# eeZeeISP_Tiny_FT230X.net
KiCad netlist of a schematic drawn in EAGLE
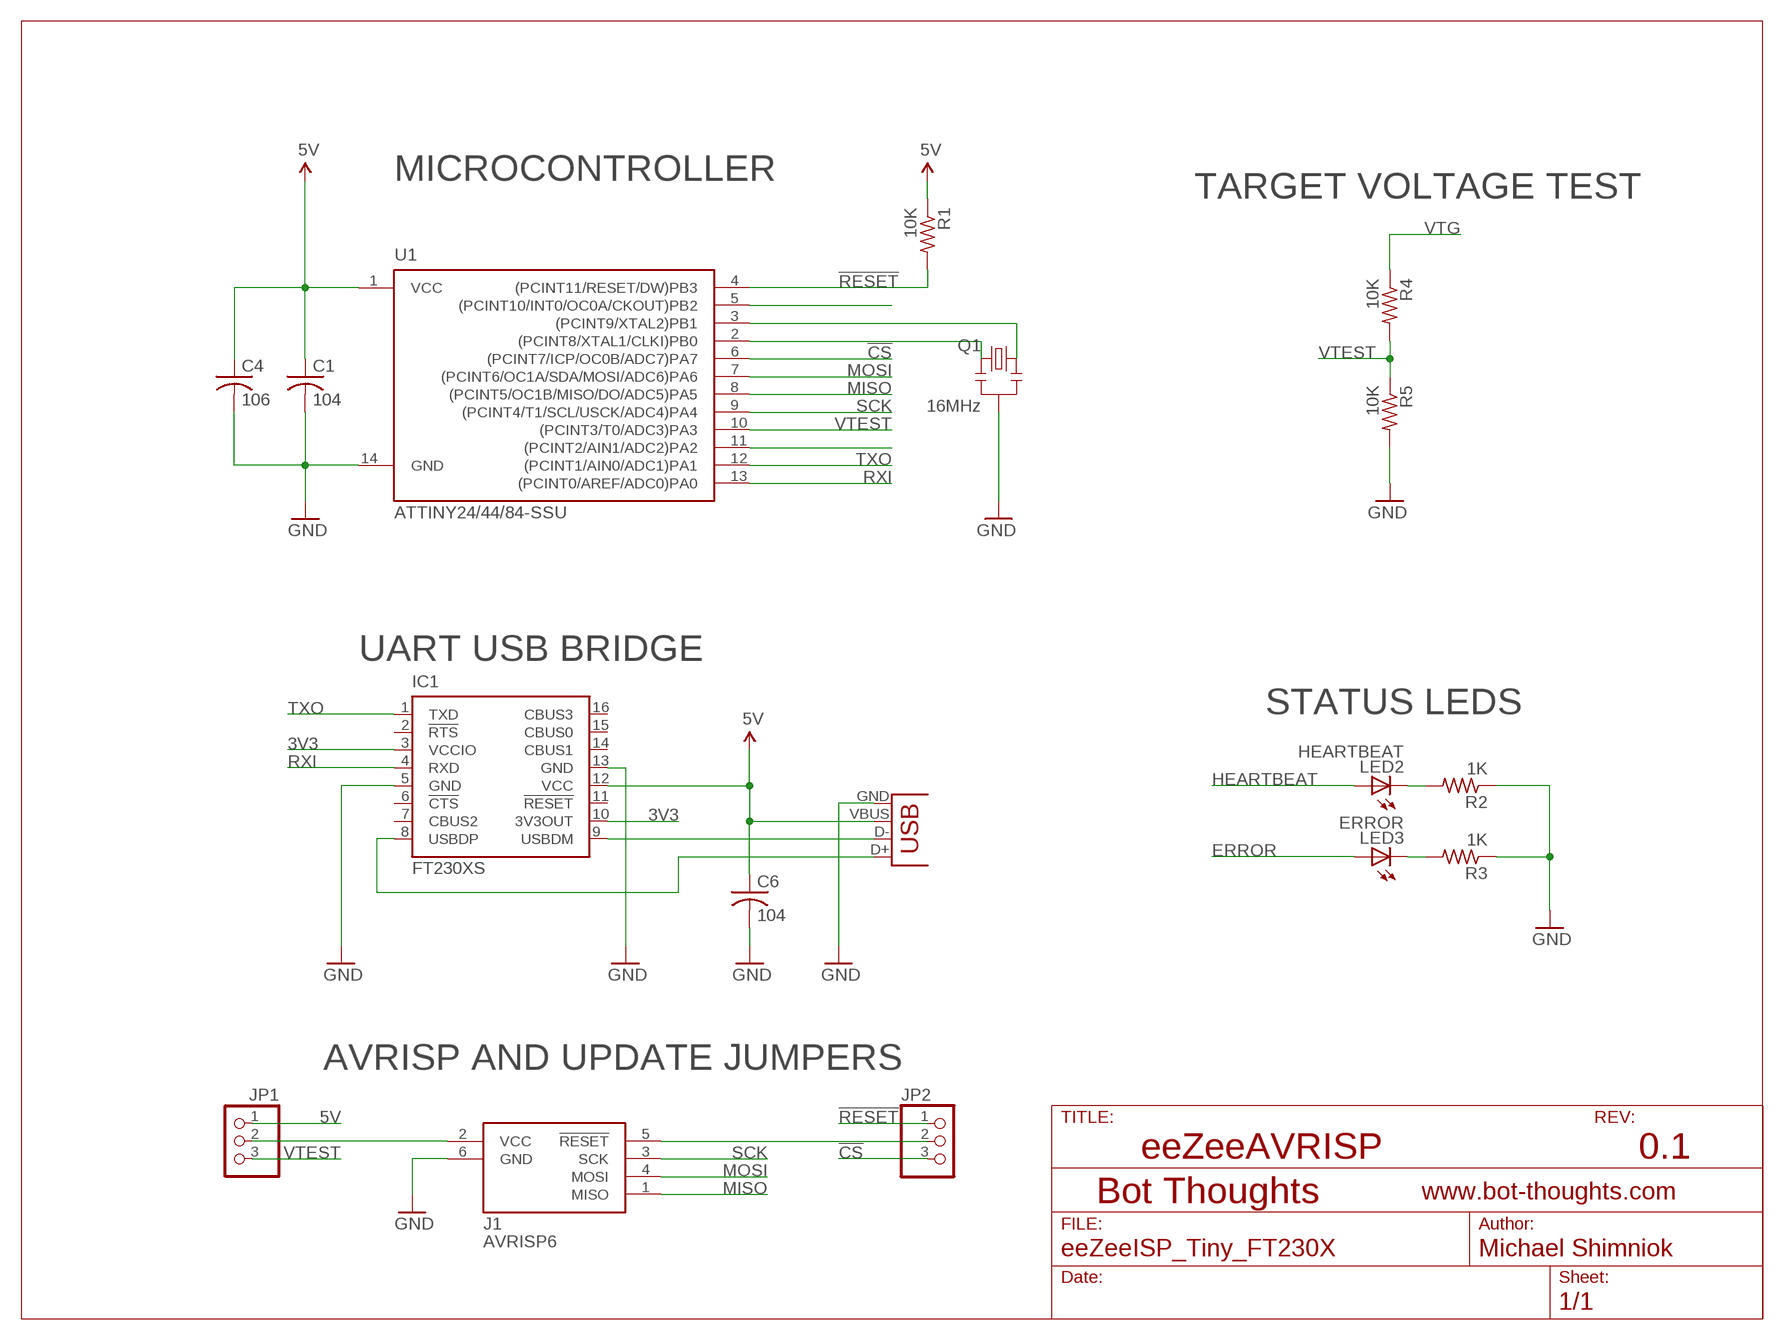
[diagram p0: schematic, sheet 1]

(export (version "E")
  (design (tool "Eeschema 10.0.6"))
  (components
    (comp (ref "C1")
      (value "104")
      (footprint "eagle-import:C0603")
      (libsource (lib "eagle-import") (part "C-USC0603"))
    )
    (comp (ref "C4")
      (value "106")
      (footprint "eagle-import:C0603")
      (libsource (lib "eagle-import") (part "C-USC0603"))
    )
    (comp (ref "C6")
      (value "104")
      (footprint "eagle-import:C0603")
      (libsource (lib "eagle-import") (part "C-USC0603"))
    )
    (comp (ref "IC1")
      (value "FT230XS")
      (footprint "eagle-import:SSOP16")
      (libsource (lib "eagle-import") (part "FT230XS"))
    )
    (comp (ref "J1")
      (value "AVRISP6")
      (footprint "eagle-import:CON6P2R")
      (libsource (lib "eagle-import") (part "AVRISP6"))
    )
    (comp (ref "JP1")
      (value "PINHD-1X03_2.00")
      (footprint "eagle-import:1X03M")
      (libsource (lib "eagle-import") (part "PINHD-1X03_2.00"))
    )
    (comp (ref "JP2")
      (value "PINHD-1X03_2.00")
      (footprint "eagle-import:1X03M")
      (libsource (lib "eagle-import") (part "PINHD-1X03_2.00"))
    )
    (comp (ref "LED2")
      (value "HEARTBEAT")
      (footprint "eagle-import:CHIPLED_1206")
      (libsource (lib "eagle-import") (part "LEDCHIPLED_1206"))
    )
    (comp (ref "LED3")
      (value "ERROR")
      (footprint "eagle-import:CHIPLED_1206")
      (libsource (lib "eagle-import") (part "LEDCHIPLED_1206"))
    )
    (comp (ref "Q1")
      (value "16MHz")
      (footprint "eagle-import:CSTCE_V_C")
      (libsource (lib "eagle-import") (part "RESONATOR_CSTCE_V_C"))
    )
    (comp (ref "R1")
      (value "10K")
      (footprint "eagle-import:R0603")
      (libsource (lib "eagle-import") (part "R-US_R0603"))
    )
    (comp (ref "R2")
      (value "1K")
      (footprint "eagle-import:R0603")
      (libsource (lib "eagle-import") (part "R-US_R0603"))
    )
    (comp (ref "R3")
      (value "1K")
      (footprint "eagle-import:R0603")
      (libsource (lib "eagle-import") (part "R-US_R0603"))
    )
    (comp (ref "R4")
      (value "10K")
      (footprint "eagle-import:R0603")
      (libsource (lib "eagle-import") (part "R-US_R0603"))
    )
    (comp (ref "R5")
      (value "10K")
      (footprint "eagle-import:R0603")
      (libsource (lib "eagle-import") (part "R-US_R0603"))
    )
    (comp (ref "U1")
      (value "ATTINY24/44/84-SSU")
      (footprint "eagle-import:SOIC14")
      (libsource (lib "eagle-import") (part "ATTINY24/44/84-SSU"))
    )
    (comp (ref "X2")
      (value "USB-SMD-NS")
      (footprint "eagle-import:USB-MINIB-NOSTOP")
      (libsource (lib "eagle-import") (part "USB-SMD-NS"))
    )
  )
  (nets
    (net (code "1") (name "/3V3") (class "Default")
      (node (ref "IC1") (pin "10") (pinfunction "3V3OUT_10") (pintype "output"))
      (node (ref "IC1") (pin "3") (pinfunction "VCCIO_3") (pintype "power_in"))
    )
    (net (code "2") (name "/ERROR") (class "Default")
      (node (ref "LED3") (pin "A") (pinfunction "A_A") (pintype "passive"))
      (node (ref "U1") (pin "11") (pinfunction "(PCINT2/AIN1/ADC2)PA2_11") (pintype "bidirectional"))
    )
    (net (code "3") (name "/HEARTBEAT") (class "Default")
      (node (ref "LED2") (pin "A") (pinfunction "A_A") (pintype "passive"))
      (node (ref "U1") (pin "5") (pinfunction "(PCINT10/INT0/OC0A/CKOUT)PB2_5") (pintype "bidirectional"))
    )
    (net (code "4") (name "/MISO") (class "Default")
      (node (ref "J1") (pin "1") (pinfunction "MISO_1") (pintype "input"))
      (node (ref "U1") (pin "8") (pinfunction "(PCINT5/OC1B/MISO/DO/ADC5)PA5_8") (pintype "bidirectional"))
    )
    (net (code "5") (name "/MOSI") (class "Default")
      (node (ref "J1") (pin "4") (pinfunction "MOSI_4") (pintype "output"))
      (node (ref "U1") (pin "7") (pinfunction "(PCINT6/OC1A/SDA/MOSI/ADC6)PA6_7") (pintype "bidirectional"))
    )
    (net (code "6") (name "/RXI") (class "Default")
      (node (ref "IC1") (pin "4") (pinfunction "RXD_4") (pintype "input"))
      (node (ref "U1") (pin "13") (pinfunction "(PCINT0/AREF/ADC0)PA0_13") (pintype "bidirectional"))
    )
    (net (code "7") (name "/SCK") (class "Default")
      (node (ref "J1") (pin "3") (pinfunction "SCK_3") (pintype "output"))
      (node (ref "U1") (pin "9") (pinfunction "(PCINT4/T1/SCL/USCK/ADC4)PA4_9") (pintype "bidirectional"))
    )
    (net (code "8") (name "/TXO") (class "Default")
      (node (ref "IC1") (pin "1") (pinfunction "TXD_1") (pintype "output"))
      (node (ref "U1") (pin "12") (pinfunction "(PCINT1/AIN0/ADC1)PA1_12") (pintype "bidirectional"))
    )
    (net (code "9") (name "/VTEST") (class "Default")
      (node (ref "JP1") (pin "3") (pinfunction "3_3") (pintype "passive"))
      (node (ref "R4") (pin "2") (pinfunction "2_2") (pintype "passive"))
      (node (ref "R5") (pin "1") (pinfunction "1_1") (pintype "passive"))
      (node (ref "U1") (pin "10") (pinfunction "(PCINT3/T0/ADC3)PA3_10") (pintype "bidirectional"))
    )
    (net (code "10") (name "/VTG") (class "Default")
      (node (ref "R4") (pin "1") (pinfunction "1_1") (pintype "passive"))
    )
    (net (code "11") (name "/~{CS}") (class "Default")
      (node (ref "JP2") (pin "3") (pinfunction "3_3") (pintype "passive"))
      (node (ref "U1") (pin "6") (pinfunction "(PCINT7/ICP/OC0B/ADC7)PA7_6") (pintype "bidirectional"))
    )
    (net (code "12") (name "/~{RESET}") (class "Default")
      (node (ref "JP2") (pin "1") (pinfunction "1_1") (pintype "passive"))
      (node (ref "R1") (pin "2") (pinfunction "2_2") (pintype "passive"))
      (node (ref "U1") (pin "4") (pinfunction "(PCINT11/RESET/DW)PB3_4") (pintype "bidirectional"))
    )
    (net (code "13") (name "5V") (class "Default")
      (node (ref "C1") (pin "1") (pinfunction "1_1") (pintype "passive"))
      (node (ref "C4") (pin "1") (pinfunction "1_1") (pintype "passive"))
      (node (ref "C6") (pin "1") (pinfunction "1_1") (pintype "passive"))
      (node (ref "IC1") (pin "12") (pinfunction "VCC_12") (pintype "power_in"))
      (node (ref "JP1") (pin "1") (pinfunction "1_1") (pintype "passive"))
      (node (ref "R1") (pin "1") (pinfunction "1_1") (pintype "passive"))
      (node (ref "U1") (pin "1") (pinfunction "VCC_1") (pintype "bidirectional"))
      (node (ref "X2") (pin "VBUS") (pinfunction "VBUS_VBUS") (pintype "bidirectional"))
    )
    (net (code "14") (name "GND") (class "Default")
      (node (ref "C1") (pin "2") (pinfunction "2_2") (pintype "passive"))
      (node (ref "C4") (pin "2") (pinfunction "2_2") (pintype "passive"))
      (node (ref "C6") (pin "2") (pinfunction "2_2") (pintype "passive"))
      (node (ref "IC1") (pin "13") (pinfunction "GND_13") (pintype "power_in"))
      (node (ref "IC1") (pin "5") (pinfunction "GND_5") (pintype "power_in"))
      (node (ref "J1") (pin "6") (pinfunction "GND_6") (pintype "power_in"))
      (node (ref "Q1") (pin "GND") (pinfunction "GND_GND") (pintype "passive"))
      (node (ref "R2") (pin "1") (pinfunction "1_1") (pintype "passive"))
      (node (ref "R3") (pin "1") (pinfunction "1_1") (pintype "passive"))
      (node (ref "R5") (pin "2") (pinfunction "2_2") (pintype "passive"))
      (node (ref "U1") (pin "14") (pinfunction "GND_14") (pintype "bidirectional"))
      (node (ref "X2") (pin "GND") (pinfunction "GND_GND") (pintype "bidirectional"))
    )
    (net (code "15") (name "Net-(IC1-USBDM)") (class "Default")
      (node (ref "IC1") (pin "9") (pinfunction "USBDM_9") (pintype "input"))
      (node (ref "X2") (pin "D-") (pinfunction "D-_D-") (pintype "bidirectional"))
    )
    (net (code "16") (name "Net-(IC1-USBDP)") (class "Default")
      (node (ref "IC1") (pin "8") (pinfunction "USBDP_8") (pintype "input"))
      (node (ref "X2") (pin "D+") (pinfunction "D+_D+") (pintype "bidirectional"))
    )
    (net (code "17") (name "Net-(J1-VCC)") (class "Default")
      (node (ref "J1") (pin "2") (pinfunction "VCC_2") (pintype "power_in"))
      (node (ref "JP1") (pin "2") (pinfunction "2_2") (pintype "passive"))
    )
    (net (code "18") (name "Net-(J1-~{RESET})") (class "Default")
      (node (ref "J1") (pin "5") (pinfunction "~{RESET}_5") (pintype "output"))
      (node (ref "JP2") (pin "2") (pinfunction "2_2") (pintype "passive"))
    )
    (net (code "19") (name "Net-(LED2-PadC)") (class "Default")
      (node (ref "LED2") (pin "C") (pinfunction "C_C") (pintype "passive"))
      (node (ref "R2") (pin "2") (pinfunction "2_2") (pintype "passive"))
    )
    (net (code "20") (name "Net-(LED3-PadC)") (class "Default")
      (node (ref "LED3") (pin "C") (pinfunction "C_C") (pintype "passive"))
      (node (ref "R3") (pin "2") (pinfunction "2_2") (pintype "passive"))
    )
    (net (code "21") (name "Net-(U1-(PCINT8{slash}XTAL1{slash}CLKI)PB0)") (class "Default")
      (node (ref "Q1") (pin "X2") (pinfunction "X2_X2") (pintype "passive"))
      (node (ref "U1") (pin "2") (pinfunction "(PCINT8/XTAL1/CLKI)PB0_2") (pintype "bidirectional"))
    )
    (net (code "22") (name "Net-(U1-(PCINT9{slash}XTAL2)PB1)") (class "Default")
      (node (ref "Q1") (pin "X1") (pinfunction "X1_X1") (pintype "passive"))
      (node (ref "U1") (pin "3") (pinfunction "(PCINT9/XTAL2)PB1_3") (pintype "bidirectional"))
    )
    (net (code "23") (name "unconnected-(IC1-CBUS0-Pad15)") (class "Default")
      (node (ref "IC1") (pin "15") (pinfunction "CBUS0_15") (pintype "bidirectional"))
    )
    (net (code "24") (name "unconnected-(IC1-CBUS1-Pad14)") (class "Default")
      (node (ref "IC1") (pin "14") (pinfunction "CBUS1_14") (pintype "bidirectional"))
    )
    (net (code "25") (name "unconnected-(IC1-CBUS2-Pad7)") (class "Default")
      (node (ref "IC1") (pin "7") (pinfunction "CBUS2_7") (pintype "bidirectional"))
    )
    (net (code "26") (name "unconnected-(IC1-CBUS3-Pad16)") (class "Default")
      (node (ref "IC1") (pin "16") (pinfunction "CBUS3_16") (pintype "bidirectional"))
    )
    (net (code "27") (name "unconnected-(IC1-~{CTS}-Pad6)") (class "Default")
      (node (ref "IC1") (pin "6") (pinfunction "~{CTS}_6") (pintype "input"))
    )
    (net (code "28") (name "unconnected-(IC1-~{RESET}-Pad11)") (class "Default")
      (node (ref "IC1") (pin "11") (pinfunction "~{RESET}_11") (pintype "input"))
    )
    (net (code "29") (name "unconnected-(IC1-~{RTS}-Pad2)") (class "Default")
      (node (ref "IC1") (pin "2") (pinfunction "~{RTS}_2") (pintype "output"))
    )
  )
)
